# PCB_schematic.net
KiCad netlist of a schematic drawn in EAGLE
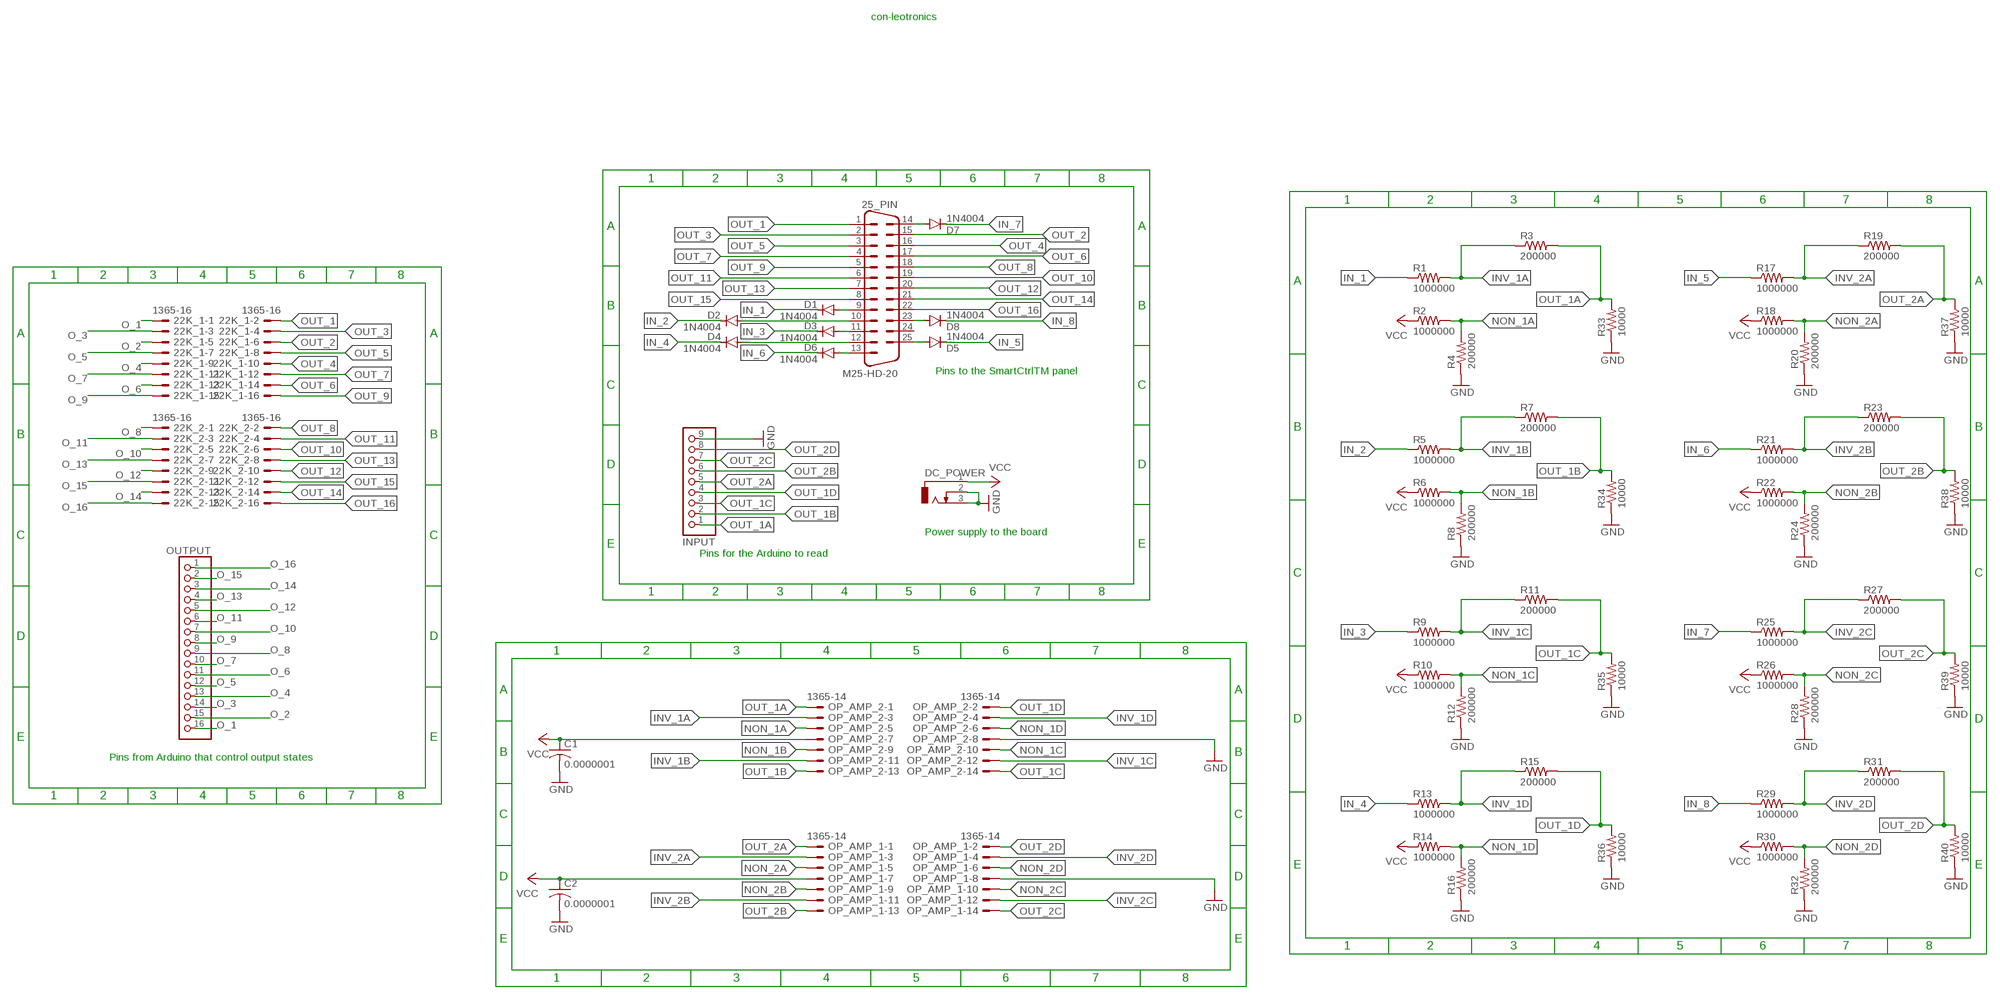
[diagram p0: schematic, sheet 1]

(export (version "E")
  (design (tool "Eeschema 10.0.6"))
  (components
    (comp (ref "22K_1")
      (value "1365-16")
      (footprint "eagle-import:1365-16")
      (libsource (lib "eagle-import") (part "1365-16"))
    )
    (comp (ref "22K_2")
      (value "1365-16")
      (footprint "eagle-import:1365-16")
      (libsource (lib "eagle-import") (part "1365-16"))
    )
    (comp (ref "25_PIN")
      (value "M25-HD-20")
      (footprint "eagle-import:M25-HD-20")
      (libsource (lib "eagle-import") (part "M25-HD-20"))
    )
    (comp (ref "C1")
      (value "0.0000001")
      (footprint "eagle-import:C1206")
      (libsource (lib "eagle-import") (part "C-USC1206"))
    )
    (comp (ref "C2")
      (value "0.0000001")
      (footprint "eagle-import:C1206")
      (libsource (lib "eagle-import") (part "C-USC1206"))
    )
    (comp (ref "D1")
      (value "1N4004")
      (footprint "eagle-import:DO41-10")
      (libsource (lib "eagle-import") (part "1N4004"))
    )
    (comp (ref "D2")
      (value "1N4004")
      (footprint "eagle-import:DO41-10")
      (libsource (lib "eagle-import") (part "1N4004"))
    )
    (comp (ref "D3")
      (value "1N4004")
      (footprint "eagle-import:DO41-10")
      (libsource (lib "eagle-import") (part "1N4004"))
    )
    (comp (ref "D4")
      (value "1N4004")
      (footprint "eagle-import:DO41-10")
      (libsource (lib "eagle-import") (part "1N4004"))
    )
    (comp (ref "D5")
      (value "1N4004")
      (footprint "eagle-import:DO41-10")
      (libsource (lib "eagle-import") (part "1N4004"))
    )
    (comp (ref "D6")
      (value "1N4004")
      (footprint "eagle-import:DO41-10")
      (libsource (lib "eagle-import") (part "1N4004"))
    )
    (comp (ref "D7")
      (value "1N4004")
      (footprint "eagle-import:DO41-10")
      (libsource (lib "eagle-import") (part "1N4004"))
    )
    (comp (ref "D8")
      (value "1N4004")
      (footprint "eagle-import:DO41-10")
      (libsource (lib "eagle-import") (part "1N4004"))
    )
    (comp (ref "DC_POWER")
      (value "DCJ0303")
      (footprint "eagle-import:DCJ0303")
      (libsource (lib "eagle-import") (part "DCJ0303"))
    )
    (comp (ref "INPUT")
      (value "PINHD-1X9")
      (footprint "eagle-import:1X09")
      (libsource (lib "eagle-import") (part "PINHD-1X9"))
    )
    (comp (ref "OP_AMP_1")
      (value "1365-14")
      (footprint "eagle-import:1365-14")
      (libsource (lib "eagle-import") (part "1365-14"))
    )
    (comp (ref "OP_AMP_2")
      (value "1365-14")
      (footprint "eagle-import:1365-14")
      (libsource (lib "eagle-import") (part "1365-14"))
    )
    (comp (ref "OUTPUT")
      (value "PINHD-1X16")
      (footprint "eagle-import:1X16")
      (libsource (lib "eagle-import") (part "PINHD-1X16"))
    )
    (comp (ref "R1")
      (value "1000000")
      (footprint "eagle-import:R1206")
      (libsource (lib "eagle-import") (part "R-US_R1206"))
    )
    (comp (ref "R2")
      (value "1000000")
      (footprint "eagle-import:R1206")
      (libsource (lib "eagle-import") (part "R-US_R1206"))
    )
    (comp (ref "R3")
      (value "200000")
      (footprint "eagle-import:R1206")
      (libsource (lib "eagle-import") (part "R-US_R1206"))
    )
    (comp (ref "R4")
      (value "200000")
      (footprint "eagle-import:R1206")
      (libsource (lib "eagle-import") (part "R-US_R1206"))
    )
    (comp (ref "R5")
      (value "1000000")
      (footprint "eagle-import:R1206")
      (libsource (lib "eagle-import") (part "R-US_R1206"))
    )
    (comp (ref "R6")
      (value "1000000")
      (footprint "eagle-import:R1206")
      (libsource (lib "eagle-import") (part "R-US_R1206"))
    )
    (comp (ref "R7")
      (value "200000")
      (footprint "eagle-import:R1206")
      (libsource (lib "eagle-import") (part "R-US_R1206"))
    )
    (comp (ref "R8")
      (value "200000")
      (footprint "eagle-import:R1206")
      (libsource (lib "eagle-import") (part "R-US_R1206"))
    )
    (comp (ref "R9")
      (value "1000000")
      (footprint "eagle-import:R1206")
      (libsource (lib "eagle-import") (part "R-US_R1206"))
    )
    (comp (ref "R10")
      (value "1000000")
      (footprint "eagle-import:R1206")
      (libsource (lib "eagle-import") (part "R-US_R1206"))
    )
    (comp (ref "R11")
      (value "200000")
      (footprint "eagle-import:R1206")
      (libsource (lib "eagle-import") (part "R-US_R1206"))
    )
    (comp (ref "R12")
      (value "200000")
      (footprint "eagle-import:R1206")
      (libsource (lib "eagle-import") (part "R-US_R1206"))
    )
    (comp (ref "R13")
      (value "1000000")
      (footprint "eagle-import:R1206")
      (libsource (lib "eagle-import") (part "R-US_R1206"))
    )
    (comp (ref "R14")
      (value "1000000")
      (footprint "eagle-import:R1206")
      (libsource (lib "eagle-import") (part "R-US_R1206"))
    )
    (comp (ref "R15")
      (value "200000")
      (footprint "eagle-import:R1206")
      (libsource (lib "eagle-import") (part "R-US_R1206"))
    )
    (comp (ref "R16")
      (value "200000")
      (footprint "eagle-import:R1206")
      (libsource (lib "eagle-import") (part "R-US_R1206"))
    )
    (comp (ref "R17")
      (value "1000000")
      (footprint "eagle-import:R1206")
      (libsource (lib "eagle-import") (part "R-US_R1206"))
    )
    (comp (ref "R18")
      (value "1000000")
      (footprint "eagle-import:R1206")
      (libsource (lib "eagle-import") (part "R-US_R1206"))
    )
    (comp (ref "R19")
      (value "200000")
      (footprint "eagle-import:R1206")
      (libsource (lib "eagle-import") (part "R-US_R1206"))
    )
    (comp (ref "R20")
      (value "200000")
      (footprint "eagle-import:R1206")
      (libsource (lib "eagle-import") (part "R-US_R1206"))
    )
    (comp (ref "R21")
      (value "1000000")
      (footprint "eagle-import:R1206")
      (libsource (lib "eagle-import") (part "R-US_R1206"))
    )
    (comp (ref "R22")
      (value "1000000")
      (footprint "eagle-import:R1206")
      (libsource (lib "eagle-import") (part "R-US_R1206"))
    )
    (comp (ref "R23")
      (value "200000")
      (footprint "eagle-import:R1206")
      (libsource (lib "eagle-import") (part "R-US_R1206"))
    )
    (comp (ref "R24")
      (value "200000")
      (footprint "eagle-import:R1206")
      (libsource (lib "eagle-import") (part "R-US_R1206"))
    )
    (comp (ref "R25")
      (value "1000000")
      (footprint "eagle-import:R1206")
      (libsource (lib "eagle-import") (part "R-US_R1206"))
    )
    (comp (ref "R26")
      (value "1000000")
      (footprint "eagle-import:R1206")
      (libsource (lib "eagle-import") (part "R-US_R1206"))
    )
    (comp (ref "R27")
      (value "200000")
      (footprint "eagle-import:R1206")
      (libsource (lib "eagle-import") (part "R-US_R1206"))
    )
    (comp (ref "R28")
      (value "200000")
      (footprint "eagle-import:R1206")
      (libsource (lib "eagle-import") (part "R-US_R1206"))
    )
    (comp (ref "R29")
      (value "1000000")
      (footprint "eagle-import:R1206")
      (libsource (lib "eagle-import") (part "R-US_R1206"))
    )
    (comp (ref "R30")
      (value "1000000")
      (footprint "eagle-import:R1206")
      (libsource (lib "eagle-import") (part "R-US_R1206"))
    )
    (comp (ref "R31")
      (value "200000")
      (footprint "eagle-import:R1206")
      (libsource (lib "eagle-import") (part "R-US_R1206"))
    )
    (comp (ref "R32")
      (value "200000")
      (footprint "eagle-import:R1206")
      (libsource (lib "eagle-import") (part "R-US_R1206"))
    )
    (comp (ref "R33")
      (value "10000")
      (footprint "eagle-import:R1206")
      (libsource (lib "eagle-import") (part "R-US_R1206"))
    )
    (comp (ref "R34")
      (value "10000")
      (footprint "eagle-import:R1206")
      (libsource (lib "eagle-import") (part "R-US_R1206"))
    )
    (comp (ref "R35")
      (value "10000")
      (footprint "eagle-import:R1206")
      (libsource (lib "eagle-import") (part "R-US_R1206"))
    )
    (comp (ref "R36")
      (value "10000")
      (footprint "eagle-import:R1206")
      (libsource (lib "eagle-import") (part "R-US_R1206"))
    )
    (comp (ref "R37")
      (value "10000")
      (footprint "eagle-import:R1206")
      (libsource (lib "eagle-import") (part "R-US_R1206"))
    )
    (comp (ref "R38")
      (value "10000")
      (footprint "eagle-import:R1206")
      (libsource (lib "eagle-import") (part "R-US_R1206"))
    )
    (comp (ref "R39")
      (value "10000")
      (footprint "eagle-import:R1206")
      (libsource (lib "eagle-import") (part "R-US_R1206"))
    )
    (comp (ref "R40")
      (value "10000")
      (footprint "eagle-import:R1206")
      (libsource (lib "eagle-import") (part "R-US_R1206"))
    )
  )
  (nets
    (net (code "1") (name "/O_1") (class "Default")
      (node (ref "22K_1") (pin "1") (pinfunction "S_1") (pintype "passive"))
      (node (ref "OUTPUT") (pin "16") (pinfunction "16_16") (pintype "passive"))
    )
    (net (code "2") (name "/O_2") (class "Default")
      (node (ref "22K_1") (pin "5") (pinfunction "S_5") (pintype "passive"))
      (node (ref "OUTPUT") (pin "15") (pinfunction "15_15") (pintype "passive"))
    )
    (net (code "3") (name "/O_3") (class "Default")
      (node (ref "22K_1") (pin "3") (pinfunction "S_3") (pintype "passive"))
      (node (ref "OUTPUT") (pin "14") (pinfunction "14_14") (pintype "passive"))
    )
    (net (code "4") (name "/O_4") (class "Default")
      (node (ref "22K_1") (pin "9") (pinfunction "S_9") (pintype "passive"))
      (node (ref "OUTPUT") (pin "13") (pinfunction "13_13") (pintype "passive"))
    )
    (net (code "5") (name "/O_5") (class "Default")
      (node (ref "22K_1") (pin "7") (pinfunction "S_7") (pintype "passive"))
      (node (ref "OUTPUT") (pin "12") (pinfunction "12_12") (pintype "passive"))
    )
    (net (code "6") (name "/O_6") (class "Default")
      (node (ref "22K_1") (pin "13") (pinfunction "S_13") (pintype "passive"))
      (node (ref "OUTPUT") (pin "11") (pinfunction "11_11") (pintype "passive"))
    )
    (net (code "7") (name "/O_7") (class "Default")
      (node (ref "22K_1") (pin "11") (pinfunction "S_11") (pintype "passive"))
      (node (ref "OUTPUT") (pin "10") (pinfunction "10_10") (pintype "passive"))
    )
    (net (code "8") (name "/O_8") (class "Default")
      (node (ref "22K_2") (pin "1") (pinfunction "S_1") (pintype "passive"))
      (node (ref "OUTPUT") (pin "9") (pinfunction "9_9") (pintype "passive"))
    )
    (net (code "9") (name "/O_9") (class "Default")
      (node (ref "22K_1") (pin "15") (pinfunction "S_15") (pintype "passive"))
      (node (ref "OUTPUT") (pin "8") (pinfunction "8_8") (pintype "passive"))
    )
    (net (code "10") (name "/O_10") (class "Default")
      (node (ref "22K_2") (pin "5") (pinfunction "S_5") (pintype "passive"))
      (node (ref "OUTPUT") (pin "7") (pinfunction "7_7") (pintype "passive"))
    )
    (net (code "11") (name "/O_11") (class "Default")
      (node (ref "22K_2") (pin "3") (pinfunction "S_3") (pintype "passive"))
      (node (ref "OUTPUT") (pin "6") (pinfunction "6_6") (pintype "passive"))
    )
    (net (code "12") (name "/O_12") (class "Default")
      (node (ref "22K_2") (pin "9") (pinfunction "S_9") (pintype "passive"))
      (node (ref "OUTPUT") (pin "5") (pinfunction "5_5") (pintype "passive"))
    )
    (net (code "13") (name "/O_13") (class "Default")
      (node (ref "22K_2") (pin "7") (pinfunction "S_7") (pintype "passive"))
      (node (ref "OUTPUT") (pin "4") (pinfunction "4_4") (pintype "passive"))
    )
    (net (code "14") (name "/O_14") (class "Default")
      (node (ref "22K_2") (pin "13") (pinfunction "S_13") (pintype "passive"))
      (node (ref "OUTPUT") (pin "3") (pinfunction "3_3") (pintype "passive"))
    )
    (net (code "15") (name "/O_15") (class "Default")
      (node (ref "22K_2") (pin "11") (pinfunction "S_11") (pintype "passive"))
      (node (ref "OUTPUT") (pin "2") (pinfunction "2_2") (pintype "passive"))
    )
    (net (code "16") (name "/O_16") (class "Default")
      (node (ref "22K_2") (pin "15") (pinfunction "S_15") (pintype "passive"))
      (node (ref "OUTPUT") (pin "1") (pinfunction "1_1") (pintype "passive"))
    )
    (net (code "17") (name "GND") (class "Default")
      (node (ref "C1") (pin "2") (pinfunction "2_2") (pintype "passive"))
      (node (ref "C2") (pin "2") (pinfunction "2_2") (pintype "passive"))
      (node (ref "DC_POWER") (pin "2") (pinfunction "2_2") (pintype "passive"))
      (node (ref "DC_POWER") (pin "3") (pinfunction "3_3") (pintype "passive"))
      (node (ref "INPUT") (pin "9") (pinfunction "9_9") (pintype "passive"))
      (node (ref "OP_AMP_1") (pin "8") (pinfunction "S_8") (pintype "passive"))
      (node (ref "OP_AMP_2") (pin "8") (pinfunction "S_8") (pintype "passive"))
      (node (ref "R12") (pin "1") (pinfunction "1_1") (pintype "passive"))
      (node (ref "R16") (pin "1") (pinfunction "1_1") (pintype "passive"))
      (node (ref "R20") (pin "1") (pinfunction "1_1") (pintype "passive"))
      (node (ref "R24") (pin "1") (pinfunction "1_1") (pintype "passive"))
      (node (ref "R28") (pin "1") (pinfunction "1_1") (pintype "passive"))
      (node (ref "R32") (pin "1") (pinfunction "1_1") (pintype "passive"))
      (node (ref "R33") (pin "1") (pinfunction "1_1") (pintype "passive"))
      (node (ref "R34") (pin "1") (pinfunction "1_1") (pintype "passive"))
      (node (ref "R35") (pin "1") (pinfunction "1_1") (pintype "passive"))
      (node (ref "R36") (pin "1") (pinfunction "1_1") (pintype "passive"))
      (node (ref "R37") (pin "1") (pinfunction "1_1") (pintype "passive"))
      (node (ref "R38") (pin "1") (pinfunction "1_1") (pintype "passive"))
      (node (ref "R39") (pin "1") (pinfunction "1_1") (pintype "passive"))
      (node (ref "R4") (pin "1") (pinfunction "1_1") (pintype "passive"))
      (node (ref "R40") (pin "1") (pinfunction "1_1") (pintype "passive"))
      (node (ref "R8") (pin "1") (pinfunction "1_1") (pintype "passive"))
    )
    (net (code "18") (name "INV_1A") (class "Default")
      (node (ref "OP_AMP_2") (pin "3") (pinfunction "S_3") (pintype "passive"))
      (node (ref "R1") (pin "2") (pinfunction "2_2") (pintype "passive"))
      (node (ref "R3") (pin "1") (pinfunction "1_1") (pintype "passive"))
    )
    (net (code "19") (name "INV_1B") (class "Default")
      (node (ref "OP_AMP_2") (pin "11") (pinfunction "S_11") (pintype "passive"))
      (node (ref "R5") (pin "2") (pinfunction "2_2") (pintype "passive"))
      (node (ref "R7") (pin "1") (pinfunction "1_1") (pintype "passive"))
    )
    (net (code "20") (name "INV_1C") (class "Default")
      (node (ref "OP_AMP_2") (pin "12") (pinfunction "S_12") (pintype "passive"))
      (node (ref "R11") (pin "1") (pinfunction "1_1") (pintype "passive"))
      (node (ref "R9") (pin "2") (pinfunction "2_2") (pintype "passive"))
    )
    (net (code "21") (name "INV_1D") (class "Default")
      (node (ref "OP_AMP_2") (pin "4") (pinfunction "S_4") (pintype "passive"))
      (node (ref "R13") (pin "2") (pinfunction "2_2") (pintype "passive"))
      (node (ref "R15") (pin "1") (pinfunction "1_1") (pintype "passive"))
    )
    (net (code "22") (name "INV_2A") (class "Default")
      (node (ref "OP_AMP_1") (pin "3") (pinfunction "S_3") (pintype "passive"))
      (node (ref "R17") (pin "2") (pinfunction "2_2") (pintype "passive"))
      (node (ref "R19") (pin "1") (pinfunction "1_1") (pintype "passive"))
    )
    (net (code "23") (name "INV_2B") (class "Default")
      (node (ref "OP_AMP_1") (pin "11") (pinfunction "S_11") (pintype "passive"))
      (node (ref "R21") (pin "2") (pinfunction "2_2") (pintype "passive"))
      (node (ref "R23") (pin "1") (pinfunction "1_1") (pintype "passive"))
    )
    (net (code "24") (name "INV_2C") (class "Default")
      (node (ref "OP_AMP_1") (pin "12") (pinfunction "S_12") (pintype "passive"))
      (node (ref "R25") (pin "2") (pinfunction "2_2") (pintype "passive"))
      (node (ref "R27") (pin "1") (pinfunction "1_1") (pintype "passive"))
    )
    (net (code "25") (name "INV_2D") (class "Default")
      (node (ref "OP_AMP_1") (pin "4") (pinfunction "S_4") (pintype "passive"))
      (node (ref "R29") (pin "2") (pinfunction "2_2") (pintype "passive"))
      (node (ref "R31") (pin "1") (pinfunction "1_1") (pintype "passive"))
    )
    (net (code "26") (name "IN_1") (class "Default")
      (node (ref "D1") (pin "C") (pinfunction "C_C") (pintype "passive"))
      (node (ref "R1") (pin "1") (pinfunction "1_1") (pintype "passive"))
    )
    (net (code "27") (name "IN_2") (class "Default")
      (node (ref "D2") (pin "C") (pinfunction "C_C") (pintype "passive"))
      (node (ref "R5") (pin "1") (pinfunction "1_1") (pintype "passive"))
    )
    (net (code "28") (name "IN_3") (class "Default")
      (node (ref "D3") (pin "C") (pinfunction "C_C") (pintype "passive"))
      (node (ref "R9") (pin "1") (pinfunction "1_1") (pintype "passive"))
    )
    (net (code "29") (name "IN_4") (class "Default")
      (node (ref "D4") (pin "C") (pinfunction "C_C") (pintype "passive"))
      (node (ref "R13") (pin "1") (pinfunction "1_1") (pintype "passive"))
    )
    (net (code "30") (name "IN_5") (class "Default")
      (node (ref "D5") (pin "C") (pinfunction "C_C") (pintype "passive"))
      (node (ref "R17") (pin "1") (pinfunction "1_1") (pintype "passive"))
    )
    (net (code "31") (name "IN_6") (class "Default")
      (node (ref "D6") (pin "C") (pinfunction "C_C") (pintype "passive"))
      (node (ref "R21") (pin "1") (pinfunction "1_1") (pintype "passive"))
    )
    (net (code "32") (name "IN_7") (class "Default")
      (node (ref "D7") (pin "C") (pinfunction "C_C") (pintype "passive"))
      (node (ref "R25") (pin "1") (pinfunction "1_1") (pintype "passive"))
    )
    (net (code "33") (name "IN_8") (class "Default")
      (node (ref "D8") (pin "C") (pinfunction "C_C") (pintype "passive"))
      (node (ref "R29") (pin "1") (pinfunction "1_1") (pintype "passive"))
    )
    (net (code "34") (name "NON_1A") (class "Default")
      (node (ref "OP_AMP_2") (pin "5") (pinfunction "S_5") (pintype "passive"))
      (node (ref "R2") (pin "2") (pinfunction "2_2") (pintype "passive"))
      (node (ref "R4") (pin "2") (pinfunction "2_2") (pintype "passive"))
    )
    (net (code "35") (name "NON_1B") (class "Default")
      (node (ref "OP_AMP_2") (pin "9") (pinfunction "S_9") (pintype "passive"))
      (node (ref "R6") (pin "2") (pinfunction "2_2") (pintype "passive"))
      (node (ref "R8") (pin "2") (pinfunction "2_2") (pintype "passive"))
    )
    (net (code "36") (name "NON_1C") (class "Default")
      (node (ref "OP_AMP_2") (pin "10") (pinfunction "S_10") (pintype "passive"))
      (node (ref "R10") (pin "2") (pinfunction "2_2") (pintype "passive"))
      (node (ref "R12") (pin "2") (pinfunction "2_2") (pintype "passive"))
    )
    (net (code "37") (name "NON_1D") (class "Default")
      (node (ref "OP_AMP_2") (pin "6") (pinfunction "S_6") (pintype "passive"))
      (node (ref "R14") (pin "2") (pinfunction "2_2") (pintype "passive"))
      (node (ref "R16") (pin "2") (pinfunction "2_2") (pintype "passive"))
    )
    (net (code "38") (name "NON_2A") (class "Default")
      (node (ref "OP_AMP_1") (pin "5") (pinfunction "S_5") (pintype "passive"))
      (node (ref "R18") (pin "2") (pinfunction "2_2") (pintype "passive"))
      (node (ref "R20") (pin "2") (pinfunction "2_2") (pintype "passive"))
    )
    (net (code "39") (name "NON_2B") (class "Default")
      (node (ref "OP_AMP_1") (pin "9") (pinfunction "S_9") (pintype "passive"))
      (node (ref "R22") (pin "2") (pinfunction "2_2") (pintype "passive"))
      (node (ref "R24") (pin "2") (pinfunction "2_2") (pintype "passive"))
    )
    (net (code "40") (name "NON_2C") (class "Default")
      (node (ref "OP_AMP_1") (pin "10") (pinfunction "S_10") (pintype "passive"))
      (node (ref "R26") (pin "2") (pinfunction "2_2") (pintype "passive"))
      (node (ref "R28") (pin "2") (pinfunction "2_2") (pintype "passive"))
    )
    (net (code "41") (name "NON_2D") (class "Default")
      (node (ref "OP_AMP_1") (pin "6") (pinfunction "S_6") (pintype "passive"))
      (node (ref "R30") (pin "2") (pinfunction "2_2") (pintype "passive"))
      (node (ref "R32") (pin "2") (pinfunction "2_2") (pintype "passive"))
    )
    (net (code "42") (name "Net-(25_PIN-Pad9)") (class "Default")
      (node (ref "25_PIN") (pin "9") (pinfunction "9_9") (pintype "passive"))
      (node (ref "D1") (pin "A") (pinfunction "A_A") (pintype "passive"))
    )
    (net (code "43") (name "Net-(25_PIN-Pad10)") (class "Default")
      (node (ref "25_PIN") (pin "10") (pinfunction "10_10") (pintype "passive"))
      (node (ref "D2") (pin "A") (pinfunction "A_A") (pintype "passive"))
    )
    (net (code "44") (name "Net-(25_PIN-Pad11)") (class "Default")
      (node (ref "25_PIN") (pin "11") (pinfunction "11_11") (pintype "passive"))
      (node (ref "D3") (pin "A") (pinfunction "A_A") (pintype "passive"))
    )
    (net (code "45") (name "Net-(25_PIN-Pad12)") (class "Default")
      (node (ref "25_PIN") (pin "12") (pinfunction "12_12") (pintype "passive"))
      (node (ref "D4") (pin "A") (pinfunction "A_A") (pintype "passive"))
    )
    (net (code "46") (name "Net-(25_PIN-Pad13)") (class "Default")
      (node (ref "25_PIN") (pin "13") (pinfunction "13_13") (pintype "passive"))
      (node (ref "D6") (pin "A") (pinfunction "A_A") (pintype "passive"))
    )
    (net (code "47") (name "Net-(25_PIN-Pad14)") (class "Default")
      (node (ref "25_PIN") (pin "14") (pinfunction "14_14") (pintype "passive"))
      (node (ref "D7") (pin "A") (pinfunction "A_A") (pintype "passive"))
    )
    (net (code "48") (name "Net-(25_PIN-Pad23)") (class "Default")
      (node (ref "25_PIN") (pin "23") (pinfunction "23_23") (pintype "passive"))
      (node (ref "D8") (pin "A") (pinfunction "A_A") (pintype "passive"))
    )
    (net (code "49") (name "Net-(25_PIN-Pad25)") (class "Default")
      (node (ref "25_PIN") (pin "25") (pinfunction "25_25") (pintype "passive"))
      (node (ref "D5") (pin "A") (pinfunction "A_A") (pintype "passive"))
    )
    (net (code "50") (name "OUT_1") (class "Default")
      (node (ref "22K_1") (pin "2") (pinfunction "S_2") (pintype "passive"))
      (node (ref "25_PIN") (pin "1") (pinfunction "1_1") (pintype "passive"))
    )
    (net (code "51") (name "OUT_1A") (class "Default")
      (node (ref "INPUT") (pin "1") (pinfunction "1_1") (pintype "passive"))
      (node (ref "OP_AMP_2") (pin "1") (pinfunction "S_1") (pintype "passive"))
      (node (ref "R3") (pin "2") (pinfunction "2_2") (pintype "passive"))
      (node (ref "R33") (pin "2") (pinfunction "2_2") (pintype "passive"))
    )
    (net (code "52") (name "OUT_1B") (class "Default")
      (node (ref "INPUT") (pin "2") (pinfunction "2_2") (pintype "passive"))
      (node (ref "OP_AMP_2") (pin "13") (pinfunction "S_13") (pintype "passive"))
      (node (ref "R34") (pin "2") (pinfunction "2_2") (pintype "passive"))
      (node (ref "R7") (pin "2") (pinfunction "2_2") (pintype "passive"))
    )
    (net (code "53") (name "OUT_1C") (class "Default")
      (node (ref "INPUT") (pin "3") (pinfunction "3_3") (pintype "passive"))
      (node (ref "OP_AMP_2") (pin "14") (pinfunction "S_14") (pintype "passive"))
      (node (ref "R11") (pin "2") (pinfunction "2_2") (pintype "passive"))
      (node (ref "R35") (pin "2") (pinfunction "2_2") (pintype "passive"))
    )
    (net (code "54") (name "OUT_1D") (class "Default")
      (node (ref "INPUT") (pin "4") (pinfunction "4_4") (pintype "passive"))
      (node (ref "OP_AMP_2") (pin "2") (pinfunction "S_2") (pintype "passive"))
      (node (ref "R15") (pin "2") (pinfunction "2_2") (pintype "passive"))
      (node (ref "R36") (pin "2") (pinfunction "2_2") (pintype "passive"))
    )
    (net (code "55") (name "OUT_2") (class "Default")
      (node (ref "22K_1") (pin "6") (pinfunction "S_6") (pintype "passive"))
      (node (ref "25_PIN") (pin "15") (pinfunction "15_15") (pintype "passive"))
    )
    (net (code "56") (name "OUT_2A") (class "Default")
      (node (ref "INPUT") (pin "5") (pinfunction "5_5") (pintype "passive"))
      (node (ref "OP_AMP_1") (pin "1") (pinfunction "S_1") (pintype "passive"))
      (node (ref "R19") (pin "2") (pinfunction "2_2") (pintype "passive"))
      (node (ref "R37") (pin "2") (pinfunction "2_2") (pintype "passive"))
    )
    (net (code "57") (name "OUT_2B") (class "Default")
      (node (ref "INPUT") (pin "6") (pinfunction "6_6") (pintype "passive"))
      (node (ref "OP_AMP_1") (pin "13") (pinfunction "S_13") (pintype "passive"))
      (node (ref "R23") (pin "2") (pinfunction "2_2") (pintype "passive"))
      (node (ref "R38") (pin "2") (pinfunction "2_2") (pintype "passive"))
    )
    (net (code "58") (name "OUT_2C") (class "Default")
      (node (ref "INPUT") (pin "7") (pinfunction "7_7") (pintype "passive"))
      (node (ref "OP_AMP_1") (pin "14") (pinfunction "S_14") (pintype "passive"))
      (node (ref "R27") (pin "2") (pinfunction "2_2") (pintype "passive"))
      (node (ref "R39") (pin "2") (pinfunction "2_2") (pintype "passive"))
    )
    (net (code "59") (name "OUT_2D") (class "Default")
      (node (ref "INPUT") (pin "8") (pinfunction "8_8") (pintype "passive"))
      (node (ref "OP_AMP_1") (pin "2") (pinfunction "S_2") (pintype "passive"))
      (node (ref "R31") (pin "2") (pinfunction "2_2") (pintype "passive"))
      (node (ref "R40") (pin "2") (pinfunction "2_2") (pintype "passive"))
    )
    (net (code "60") (name "OUT_3") (class "Default")
      (node (ref "22K_1") (pin "4") (pinfunction "S_4") (pintype "passive"))
      (node (ref "25_PIN") (pin "2") (pinfunction "2_2") (pintype "passive"))
    )
    (net (code "61") (name "OUT_4") (class "Default")
      (node (ref "22K_1") (pin "10") (pinfunction "S_10") (pintype "passive"))
      (node (ref "25_PIN") (pin "16") (pinfunction "16_16") (pintype "passive"))
    )
    (net (code "62") (name "OUT_5") (class "Default")
      (node (ref "22K_1") (pin "8") (pinfunction "S_8") (pintype "passive"))
      (node (ref "25_PIN") (pin "3") (pinfunction "3_3") (pintype "passive"))
    )
    (net (code "63") (name "OUT_6") (class "Default")
      (node (ref "22K_1") (pin "14") (pinfunction "S_14") (pintype "passive"))
      (node (ref "25_PIN") (pin "17") (pinfunction "17_17") (pintype "passive"))
    )
    (net (code "64") (name "OUT_7") (class "Default")
      (node (ref "22K_1") (pin "12") (pinfunction "S_12") (pintype "passive"))
      (node (ref "25_PIN") (pin "4") (pinfunction "4_4") (pintype "passive"))
    )
    (net (code "65") (name "OUT_8") (class "Default")
      (node (ref "22K_2") (pin "2") (pinfunction "S_2") (pintype "passive"))
      (node (ref "25_PIN") (pin "18") (pinfunction "18_18") (pintype "passive"))
    )
    (net (code "66") (name "OUT_9") (class "Default")
      (node (ref "22K_1") (pin "16") (pinfunction "S_16") (pintype "passive"))
      (node (ref "25_PIN") (pin "5") (pinfunction "5_5") (pintype "passive"))
    )
    (net (code "67") (name "OUT_10") (class "Default")
      (node (ref "22K_2") (pin "6") (pinfunction "S_6") (pintype "passive"))
      (node (ref "25_PIN") (pin "19") (pinfunction "19_19") (pintype "passive"))
    )
    (net (code "68") (name "OUT_11") (class "Default")
      (node (ref "22K_2") (pin "4") (pinfunction "S_4") (pintype "passive"))
      (node (ref "25_PIN") (pin "6") (pinfunction "6_6") (pintype "passive"))
    )
    (net (code "69") (name "OUT_12") (class "Default")
      (node (ref "22K_2") (pin "10") (pinfunction "S_10") (pintype "passive"))
      (node (ref "25_PIN") (pin "20") (pinfunction "20_20") (pintype "passive"))
    )
    (net (code "70") (name "OUT_13") (class "Default")
      (node (ref "22K_2") (pin "8") (pinfunction "S_8") (pintype "passive"))
      (node (ref "25_PIN") (pin "7") (pinfunction "7_7") (pintype "passive"))
    )
    (net (code "71") (name "OUT_14") (class "Default")
      (node (ref "22K_2") (pin "14") (pinfunction "S_14") (pintype "passive"))
      (node (ref "25_PIN") (pin "21") (pinfunction "21_21") (pintype "passive"))
    )
    (net (code "72") (name "OUT_15") (class "Default")
      (node (ref "22K_2") (pin "12") (pinfunction "S_12") (pintype "passive"))
      (node (ref "25_PIN") (pin "8") (pinfunction "8_8") (pintype "passive"))
    )
    (net (code "73") (name "OUT_16") (class "Default")
      (node (ref "22K_2") (pin "16") (pinfunction "S_16") (pintype "passive"))
      (node (ref "25_PIN") (pin "22") (pinfunction "22_22") (pintype "passive"))
    )
    (net (code "74") (name "VCC") (class "Default")
      (node (ref "C1") (pin "1") (pinfunction "1_1") (pintype "passive"))
      (node (ref "C2") (pin "1") (pinfunction "1_1") (pintype "passive"))
      (node (ref "DC_POWER") (pin "1") (pinfunction "1_1") (pintype "passive"))
      (node (ref "OP_AMP_1") (pin "7") (pinfunction "S_7") (pintype "passive"))
      (node (ref "OP_AMP_2") (pin "7") (pinfunction "S_7") (pintype "passive"))
      (node (ref "R10") (pin "1") (pinfunction "1_1") (pintype "passive"))
      (node (ref "R14") (pin "1") (pinfunction "1_1") (pintype "passive"))
      (node (ref "R18") (pin "1") (pinfunction "1_1") (pintype "passive"))
      (node (ref "R2") (pin "1") (pinfunction "1_1") (pintype "passive"))
      (node (ref "R22") (pin "1") (pinfunction "1_1") (pintype "passive"))
      (node (ref "R26") (pin "1") (pinfunction "1_1") (pintype "passive"))
      (node (ref "R30") (pin "1") (pinfunction "1_1") (pintype "passive"))
      (node (ref "R6") (pin "1") (pinfunction "1_1") (pintype "passive"))
    )
    (net (code "75") (name "unconnected-(25_PIN-Pad24)") (class "Default")
      (node (ref "25_PIN") (pin "24") (pinfunction "24_24") (pintype "passive"))
    )
  )
)
